# DSP.net
KiCad netlist of a schematic drawn in EAGLE
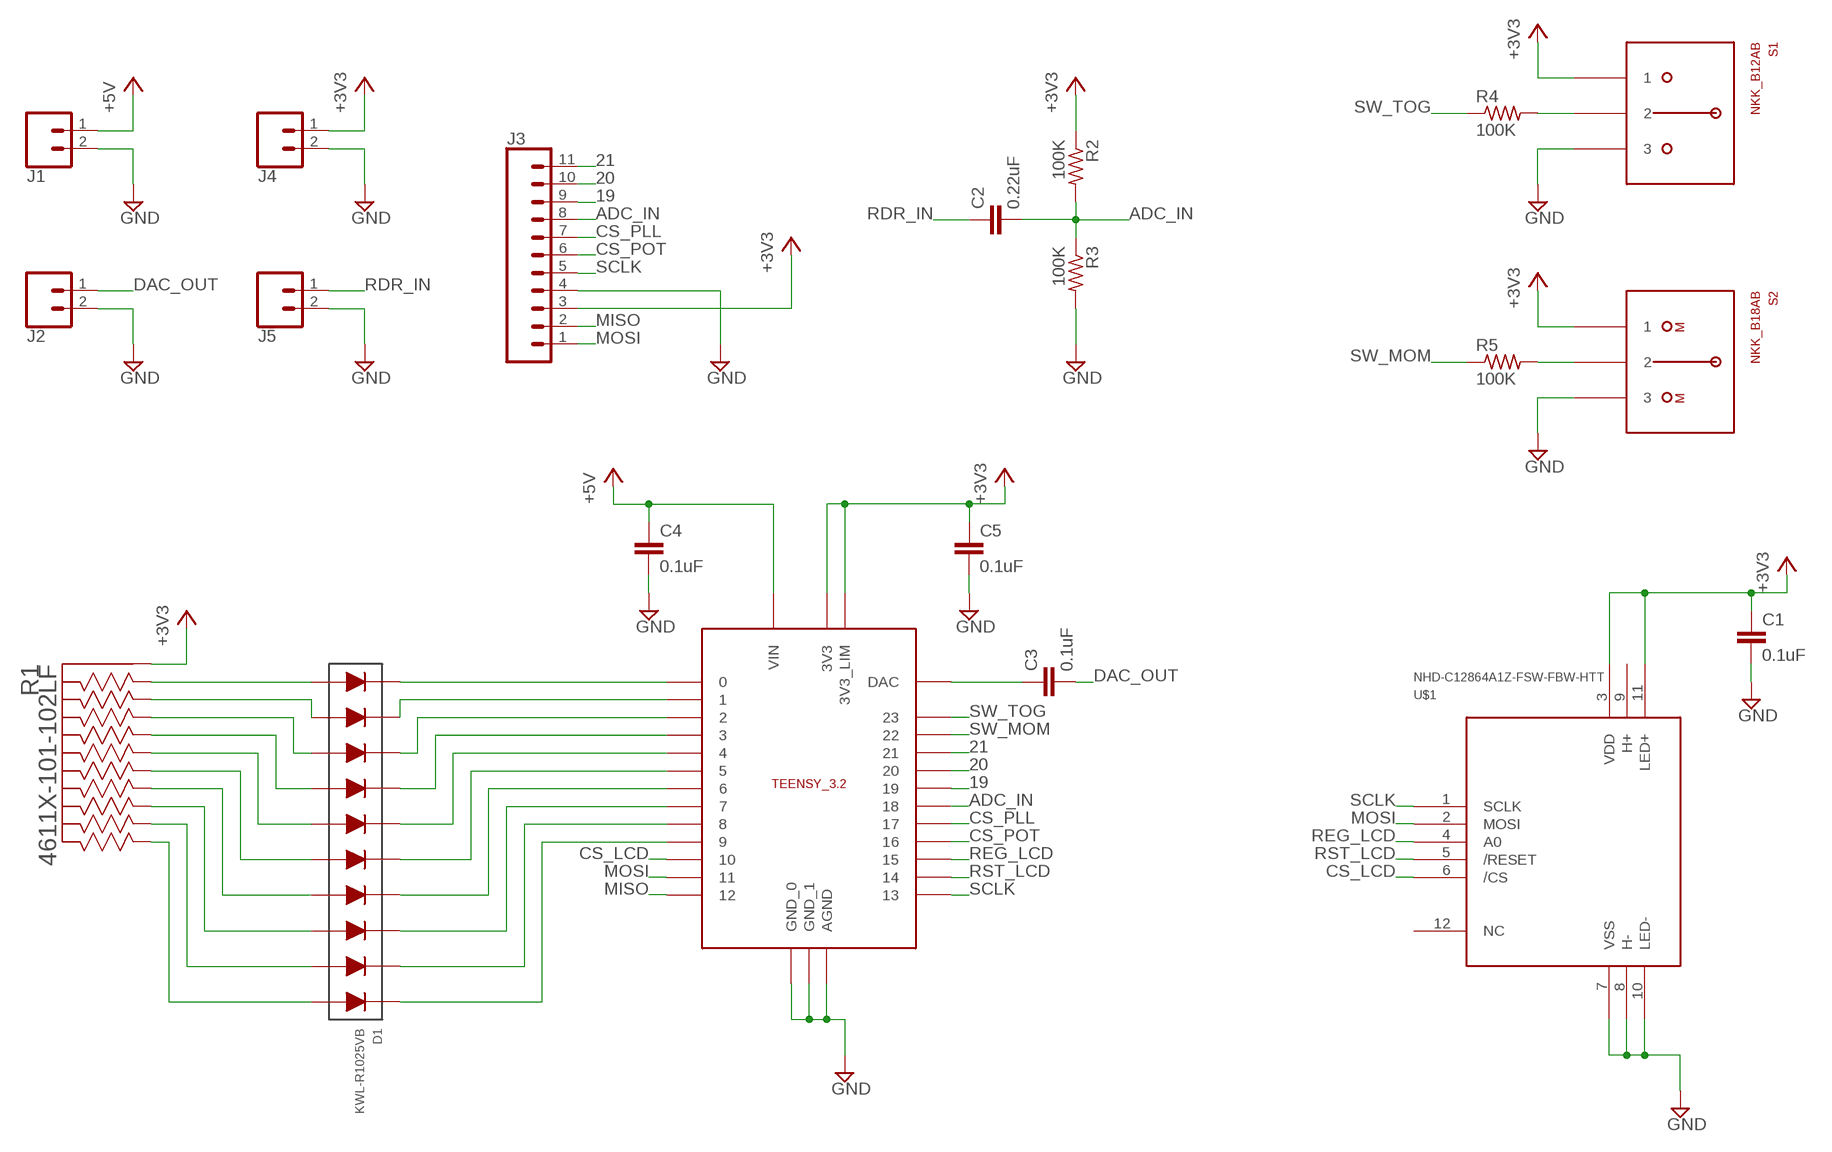
[diagram p0: schematic, sheet 1]

(export (version "E")
  (design (tool "Eeschema 10.0.6"))
  (components
    (comp (ref "C1")
      (value "0.1uF")
      (footprint "eagle-import:0603")
      (libsource (lib "eagle-import") (part "C0603"))
    )
    (comp (ref "C2")
      (value "0.22uF")
      (footprint "eagle-import:0603")
      (libsource (lib "eagle-import") (part "C0603"))
    )
    (comp (ref "C3")
      (value "0.1uF")
      (footprint "eagle-import:0603")
      (libsource (lib "eagle-import") (part "C0603"))
    )
    (comp (ref "C4")
      (value "0.1uF")
      (footprint "eagle-import:0603")
      (libsource (lib "eagle-import") (part "C0603"))
    )
    (comp (ref "C5")
      (value "0.1uF")
      (footprint "eagle-import:0603")
      (libsource (lib "eagle-import") (part "C0603"))
    )
    (comp (ref "D1")
      (value "KWL-R1025VB")
      (footprint "eagle-import:KWL-R1025VB")
      (libsource (lib "eagle-import") (part "KWL-R1025VB"))
    )
    (comp (ref "J1")
      (value "CONN_02")
      (footprint "eagle-import:1X02")
      (libsource (lib "eagle-import") (part "CONN_02"))
    )
    (comp (ref "J2")
      (value "CONN_02")
      (footprint "eagle-import:1X02")
      (libsource (lib "eagle-import") (part "CONN_02"))
    )
    (comp (ref "J3")
      (value "CONN_11")
      (footprint "eagle-import:1X11")
      (libsource (lib "eagle-import") (part "CONN_11"))
    )
    (comp (ref "J4")
      (value "CONN_02")
      (footprint "eagle-import:1X02")
      (libsource (lib "eagle-import") (part "CONN_02"))
    )
    (comp (ref "J5")
      (value "CONN_02")
      (footprint "eagle-import:1X02")
      (libsource (lib "eagle-import") (part "CONN_02"))
    )
    (comp (ref "R1")
      (value "4611X-101-102LF")
      (footprint "eagle-import:BO_4611X")
      (fields (field (name "MANUFACTURER_PART_NUMBER") "4611X101102LF"))
      (libsource (lib "eagle-import") (part "4611X-101-102LF"))
    )
    (comp (ref "R2")
      (value "100K")
      (footprint "eagle-import:0603")
      (libsource (lib "eagle-import") (part "R0603"))
    )
    (comp (ref "R3")
      (value "100K")
      (footprint "eagle-import:0603")
      (libsource (lib "eagle-import") (part "R0603"))
    )
    (comp (ref "R4")
      (value "100K")
      (footprint "eagle-import:0603")
      (libsource (lib "eagle-import") (part "R0603"))
    )
    (comp (ref "R5")
      (value "100K")
      (footprint "eagle-import:0603")
      (libsource (lib "eagle-import") (part "R0603"))
    )
    (comp (ref "S1")
      (value "NKK_B12AB")
      (footprint "eagle-import:NKK_SPDT_BRKT")
      (libsource (lib "eagle-import") (part "NKK_B12AB"))
    )
    (comp (ref "S2")
      (value "NKK_B18AB")
      (footprint "eagle-import:NKK_SPDT_BRKT")
      (libsource (lib "eagle-import") (part "NKK_B18AB"))
    )
    (comp (ref "TEENSY_3.2")
      (value "TEENSY_3.2_SOCKET")
      (footprint "eagle-import:TEENSY_3.2_SOCKET")
      (libsource (lib "eagle-import") (part "TEENSY_3.2_SOCKET"))
    )
    (comp (ref "U$1")
      (value "NHD-C12864A1Z-FSW-FBW-HTT")
      (footprint "eagle-import:NHD-C12864A1Z-FSW-FBW-HTT")
      (libsource (lib "eagle-import") (part "NHD-C12864A1Z-FSW-FBW-HTT"))
    )
  )
  (nets
    (net (code "1") (name "+3V3") (class "Default")
      (node (ref "C1") (pin "1") (pinfunction "1_1") (pintype "passive"))
      (node (ref "C5") (pin "1") (pinfunction "1_1") (pintype "passive"))
      (node (ref "J3") (pin "3") (pinfunction "3_3") (pintype "passive"))
      (node (ref "J4") (pin "1") (pinfunction "1_1") (pintype "passive"))
      (node (ref "R1") (pin "1") (pinfunction "1_1") (pintype "passive"))
      (node (ref "R2") (pin "1") (pinfunction "1_1") (pintype "passive"))
      (node (ref "S1") (pin "3") (pinfunction "1_3") (pintype "passive"))
      (node (ref "S2") (pin "3") (pinfunction "1_3") (pintype "passive"))
      (node (ref "TEENSY_3.2") (pin "3V3") (pinfunction "3V3_3V3") (pintype "bidirectional"))
      (node (ref "TEENSY_3.2") (pin "3V3_LIM") (pinfunction "3V3_LIM_3V3_LIM") (pintype "bidirectional"))
      (node (ref "U$1") (pin "11") (pinfunction "LED+_11") (pintype "passive"))
      (node (ref "U$1") (pin "3") (pinfunction "VDD_3") (pintype "passive"))
    )
    (net (code "2") (name "+5V") (class "Default")
      (node (ref "C4") (pin "1") (pinfunction "1_1") (pintype "passive"))
      (node (ref "J1") (pin "1") (pinfunction "1_1") (pintype "passive"))
      (node (ref "TEENSY_3.2") (pin "VIN") (pinfunction "VIN_VIN") (pintype "bidirectional"))
    )
    (net (code "3") (name "/19") (class "Default")
      (node (ref "J3") (pin "9") (pinfunction "9_9") (pintype "passive"))
      (node (ref "TEENSY_3.2") (pin "19") (pinfunction "19_19") (pintype "bidirectional"))
    )
    (net (code "4") (name "/20") (class "Default")
      (node (ref "J3") (pin "10") (pinfunction "10_10") (pintype "passive"))
      (node (ref "TEENSY_3.2") (pin "20") (pinfunction "20_20") (pintype "bidirectional"))
    )
    (net (code "5") (name "/21") (class "Default")
      (node (ref "J3") (pin "11") (pinfunction "11_11") (pintype "passive"))
      (node (ref "TEENSY_3.2") (pin "21") (pinfunction "21_21") (pintype "bidirectional"))
    )
    (net (code "6") (name "/ADC_IN") (class "Default")
      (node (ref "C2") (pin "2") (pinfunction "2_2") (pintype "passive"))
      (node (ref "J3") (pin "8") (pinfunction "8_8") (pintype "passive"))
      (node (ref "R2") (pin "2") (pinfunction "2_2") (pintype "passive"))
      (node (ref "R3") (pin "1") (pinfunction "1_1") (pintype "passive"))
      (node (ref "TEENSY_3.2") (pin "18") (pinfunction "18_18") (pintype "bidirectional"))
    )
    (net (code "7") (name "/CS_LCD") (class "Default")
      (node (ref "TEENSY_3.2") (pin "10") (pinfunction "10_10") (pintype "bidirectional"))
      (node (ref "U$1") (pin "6") (pinfunction "/CS_6") (pintype "passive"))
    )
    (net (code "8") (name "/CS_PLL") (class "Default")
      (node (ref "J3") (pin "7") (pinfunction "7_7") (pintype "passive"))
      (node (ref "TEENSY_3.2") (pin "17") (pinfunction "17_17") (pintype "bidirectional"))
    )
    (net (code "9") (name "/CS_POT") (class "Default")
      (node (ref "J3") (pin "6") (pinfunction "6_6") (pintype "passive"))
      (node (ref "TEENSY_3.2") (pin "16") (pinfunction "16_16") (pintype "bidirectional"))
    )
    (net (code "10") (name "/DAC_OUT") (class "Default")
      (node (ref "C3") (pin "2") (pinfunction "2_2") (pintype "passive"))
      (node (ref "J2") (pin "1") (pinfunction "1_1") (pintype "passive"))
    )
    (net (code "11") (name "/MISO") (class "Default")
      (node (ref "J3") (pin "2") (pinfunction "2_2") (pintype "passive"))
      (node (ref "TEENSY_3.2") (pin "12") (pinfunction "12_12") (pintype "bidirectional"))
    )
    (net (code "12") (name "/MOSI") (class "Default")
      (node (ref "J3") (pin "1") (pinfunction "1_1") (pintype "passive"))
      (node (ref "TEENSY_3.2") (pin "11") (pinfunction "11_11") (pintype "bidirectional"))
      (node (ref "U$1") (pin "2") (pinfunction "MOSI_2") (pintype "passive"))
    )
    (net (code "13") (name "/RDR_IN") (class "Default")
      (node (ref "C2") (pin "1") (pinfunction "1_1") (pintype "passive"))
      (node (ref "J5") (pin "1") (pinfunction "1_1") (pintype "passive"))
    )
    (net (code "14") (name "/REG_LCD") (class "Default")
      (node (ref "TEENSY_3.2") (pin "15") (pinfunction "15_15") (pintype "bidirectional"))
      (node (ref "U$1") (pin "4") (pinfunction "A0_4") (pintype "passive"))
    )
    (net (code "15") (name "/RST_LCD") (class "Default")
      (node (ref "TEENSY_3.2") (pin "14") (pinfunction "14_14") (pintype "bidirectional"))
      (node (ref "U$1") (pin "5") (pinfunction "/RESET_5") (pintype "passive"))
    )
    (net (code "16") (name "/SCLK") (class "Default")
      (node (ref "J3") (pin "5") (pinfunction "5_5") (pintype "passive"))
      (node (ref "TEENSY_3.2") (pin "13") (pinfunction "13_13") (pintype "bidirectional"))
      (node (ref "U$1") (pin "1") (pinfunction "SCLK_1") (pintype "passive"))
    )
    (net (code "17") (name "/SW_MOM") (class "Default")
      (node (ref "R5") (pin "1") (pinfunction "1_1") (pintype "passive"))
      (node (ref "TEENSY_3.2") (pin "22") (pinfunction "22_22") (pintype "bidirectional"))
    )
    (net (code "18") (name "/SW_TOG") (class "Default")
      (node (ref "R4") (pin "1") (pinfunction "1_1") (pintype "passive"))
      (node (ref "TEENSY_3.2") (pin "23") (pinfunction "23_23") (pintype "bidirectional"))
    )
    (net (code "19") (name "GND") (class "Default")
      (node (ref "C1") (pin "2") (pinfunction "2_2") (pintype "passive"))
      (node (ref "C4") (pin "2") (pinfunction "2_2") (pintype "passive"))
      (node (ref "C5") (pin "2") (pinfunction "2_2") (pintype "passive"))
      (node (ref "J1") (pin "2") (pinfunction "2_2") (pintype "passive"))
      (node (ref "J2") (pin "2") (pinfunction "2_2") (pintype "passive"))
      (node (ref "J3") (pin "4") (pinfunction "4_4") (pintype "passive"))
      (node (ref "J4") (pin "2") (pinfunction "2_2") (pintype "passive"))
      (node (ref "J5") (pin "2") (pinfunction "2_2") (pintype "passive"))
      (node (ref "R3") (pin "2") (pinfunction "2_2") (pintype "passive"))
      (node (ref "S1") (pin "5") (pinfunction "3_5") (pintype "passive"))
      (node (ref "S2") (pin "5") (pinfunction "3_5") (pintype "passive"))
      (node (ref "TEENSY_3.2") (pin "AGND") (pinfunction "AGND_AGND") (pintype "bidirectional"))
      (node (ref "TEENSY_3.2") (pin "GND_0") (pinfunction "GND_0_GND_0") (pintype "bidirectional"))
      (node (ref "TEENSY_3.2") (pin "GND_1") (pinfunction "GND_1_GND_1") (pintype "bidirectional"))
      (node (ref "U$1") (pin "10") (pinfunction "LED-_10") (pintype "passive"))
      (node (ref "U$1") (pin "7") (pinfunction "VSS_7") (pintype "passive"))
      (node (ref "U$1") (pin "8") (pinfunction "H-_8") (pintype "passive"))
    )
    (net (code "20") (name "Net-(C3-Pad1)") (class "Default")
      (node (ref "C3") (pin "1") (pinfunction "1_1") (pintype "passive"))
      (node (ref "TEENSY_3.2") (pin "DAC") (pinfunction "DAC_DAC") (pintype "bidirectional"))
    )
    (net (code "21") (name "Net-(D1-P$1)") (class "Default")
      (node (ref "D1") (pin "1+") (pinfunction "P$1_1+") (pintype "bidirectional"))
      (node (ref "R1") (pin "2") (pinfunction "2_2") (pintype "passive"))
    )
    (net (code "22") (name "Net-(D1-P$2)") (class "Default")
      (node (ref "D1") (pin "2+") (pinfunction "P$2_2+") (pintype "bidirectional"))
      (node (ref "R1") (pin "3") (pinfunction "3_3") (pintype "passive"))
    )
    (net (code "23") (name "Net-(D1-P$3)") (class "Default")
      (node (ref "D1") (pin "3+") (pinfunction "P$3_3+") (pintype "bidirectional"))
      (node (ref "R1") (pin "4") (pinfunction "4_4") (pintype "passive"))
    )
    (net (code "24") (name "Net-(D1-P$4)") (class "Default")
      (node (ref "D1") (pin "4+") (pinfunction "P$4_4+") (pintype "bidirectional"))
      (node (ref "R1") (pin "5") (pinfunction "5_5") (pintype "passive"))
    )
    (net (code "25") (name "Net-(D1-P$5)") (class "Default")
      (node (ref "D1") (pin "5+") (pinfunction "P$5_5+") (pintype "bidirectional"))
      (node (ref "R1") (pin "6") (pinfunction "6_6") (pintype "passive"))
    )
    (net (code "26") (name "Net-(D1-P$6)") (class "Default")
      (node (ref "D1") (pin "6+") (pinfunction "P$6_6+") (pintype "bidirectional"))
      (node (ref "R1") (pin "7") (pinfunction "7_7") (pintype "passive"))
    )
    (net (code "27") (name "Net-(D1-P$7)") (class "Default")
      (node (ref "D1") (pin "7+") (pinfunction "P$7_7+") (pintype "bidirectional"))
      (node (ref "R1") (pin "8") (pinfunction "8_8") (pintype "passive"))
    )
    (net (code "28") (name "Net-(D1-P$8)") (class "Default")
      (node (ref "D1") (pin "8+") (pinfunction "P$8_8+") (pintype "bidirectional"))
      (node (ref "R1") (pin "9") (pinfunction "9_9") (pintype "passive"))
    )
    (net (code "29") (name "Net-(D1-P$9)") (class "Default")
      (node (ref "D1") (pin "9+") (pinfunction "P$9_9+") (pintype "bidirectional"))
      (node (ref "R1") (pin "10") (pinfunction "10_10") (pintype "passive"))
    )
    (net (code "30") (name "Net-(D1-P$10)") (class "Default")
      (node (ref "D1") (pin "10+") (pinfunction "P$10_10+") (pintype "bidirectional"))
      (node (ref "R1") (pin "11") (pinfunction "11_11") (pintype "passive"))
    )
    (net (code "31") (name "Net-(D1-P$11)") (class "Default")
      (node (ref "D1") (pin "10-") (pinfunction "P$11_10-") (pintype "bidirectional"))
      (node (ref "TEENSY_3.2") (pin "9") (pinfunction "9_9") (pintype "bidirectional"))
    )
    (net (code "32") (name "Net-(D1-P$12)") (class "Default")
      (node (ref "D1") (pin "9-") (pinfunction "P$12_9-") (pintype "bidirectional"))
      (node (ref "TEENSY_3.2") (pin "8") (pinfunction "8_8") (pintype "bidirectional"))
    )
    (net (code "33") (name "Net-(D1-P$13)") (class "Default")
      (node (ref "D1") (pin "8-") (pinfunction "P$13_8-") (pintype "bidirectional"))
      (node (ref "TEENSY_3.2") (pin "7") (pinfunction "7_7") (pintype "bidirectional"))
    )
    (net (code "34") (name "Net-(D1-P$14)") (class "Default")
      (node (ref "D1") (pin "7-") (pinfunction "P$14_7-") (pintype "bidirectional"))
      (node (ref "TEENSY_3.2") (pin "6") (pinfunction "6_6") (pintype "bidirectional"))
    )
    (net (code "35") (name "Net-(D1-P$15)") (class "Default")
      (node (ref "D1") (pin "6-") (pinfunction "P$15_6-") (pintype "bidirectional"))
      (node (ref "TEENSY_3.2") (pin "5") (pinfunction "5_5") (pintype "bidirectional"))
    )
    (net (code "36") (name "Net-(D1-P$16)") (class "Default")
      (node (ref "D1") (pin "5-") (pinfunction "P$16_5-") (pintype "bidirectional"))
      (node (ref "TEENSY_3.2") (pin "4") (pinfunction "4_4") (pintype "bidirectional"))
    )
    (net (code "37") (name "Net-(D1-P$17)") (class "Default")
      (node (ref "D1") (pin "4-") (pinfunction "P$17_4-") (pintype "bidirectional"))
      (node (ref "TEENSY_3.2") (pin "3") (pinfunction "3_3") (pintype "bidirectional"))
    )
    (net (code "38") (name "Net-(D1-P$18)") (class "Default")
      (node (ref "D1") (pin "3-") (pinfunction "P$18_3-") (pintype "bidirectional"))
      (node (ref "TEENSY_3.2") (pin "2") (pinfunction "2_2") (pintype "bidirectional"))
    )
    (net (code "39") (name "Net-(D1-P$19)") (class "Default")
      (node (ref "D1") (pin "2-") (pinfunction "P$19_2-") (pintype "bidirectional"))
      (node (ref "TEENSY_3.2") (pin "1") (pinfunction "1_1") (pintype "bidirectional"))
    )
    (net (code "40") (name "Net-(D1-P$20)") (class "Default")
      (node (ref "D1") (pin "1-") (pinfunction "P$20_1-") (pintype "bidirectional"))
      (node (ref "TEENSY_3.2") (pin "0") (pinfunction "0_0") (pintype "bidirectional"))
    )
    (net (code "41") (name "Net-(S1-2)") (class "Default")
      (node (ref "R4") (pin "2") (pinfunction "2_2") (pintype "passive"))
      (node (ref "S1") (pin "4") (pinfunction "2_4") (pintype "passive"))
    )
    (net (code "42") (name "Net-(S2-2)") (class "Default")
      (node (ref "R5") (pin "2") (pinfunction "2_2") (pintype "passive"))
      (node (ref "S2") (pin "4") (pinfunction "2_4") (pintype "passive"))
    )
    (net (code "43") (name "unconnected-(U$1-H+-Pad9)") (class "Default")
      (node (ref "U$1") (pin "9") (pinfunction "H+_9") (pintype "passive"))
    )
    (net (code "44") (name "unconnected-(U$1-NC-Pad12)") (class "Default")
      (node (ref "U$1") (pin "12") (pinfunction "NC_12") (pintype "no_connect"))
    )
  )
)
